# power.net
KiCad netlist of a schematic drawn in Altium Designer
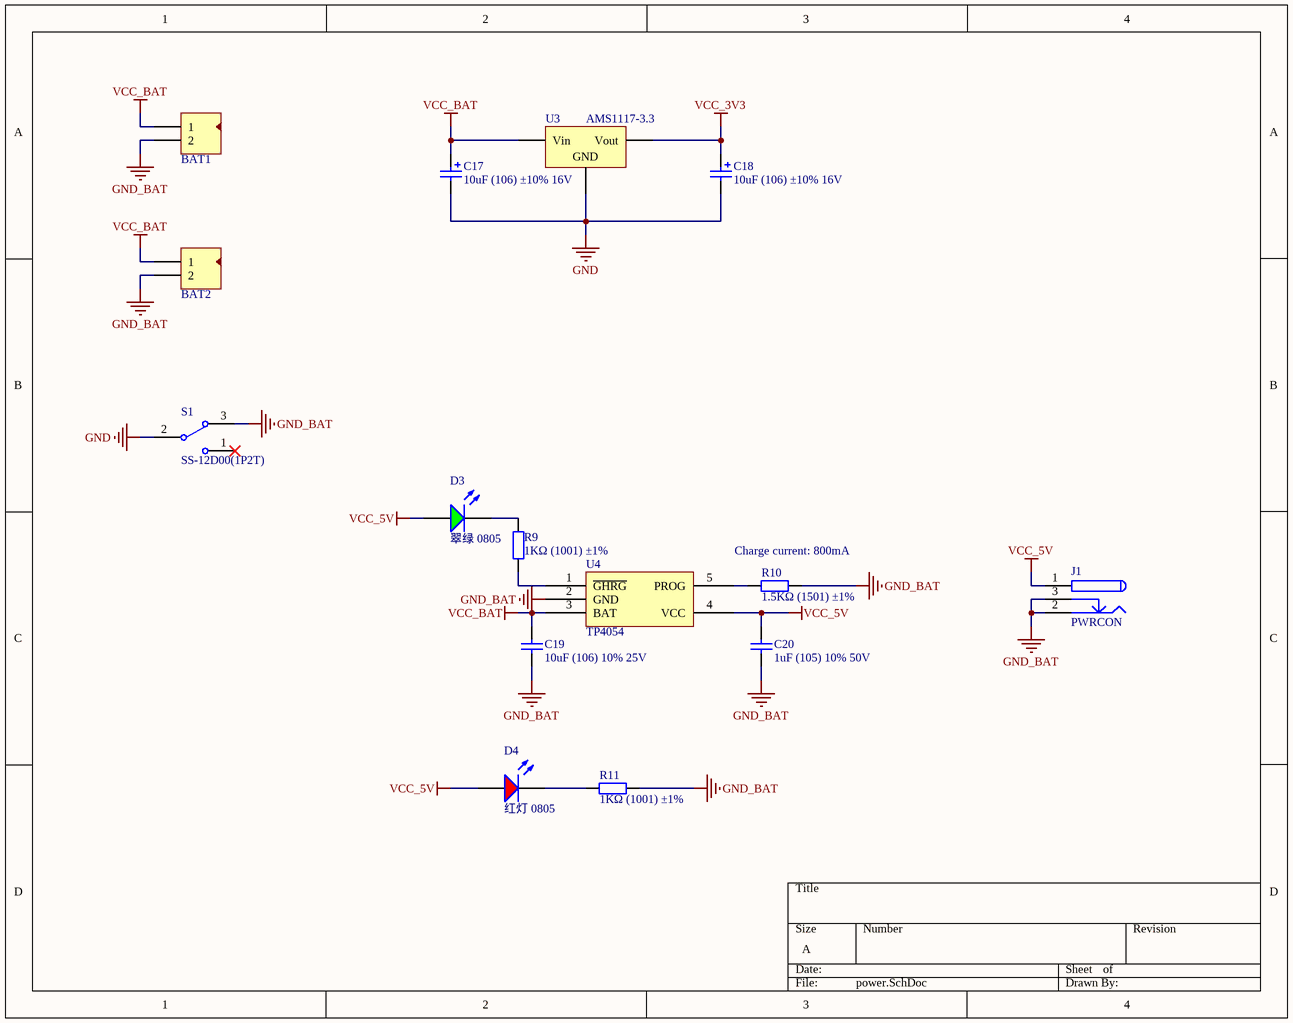
[diagram p0: power.SchDoc]

(export (version "E")
  (design (tool "Eeschema 10.0.6"))
  (components
    (comp (ref "C17")
      (value "10uF (106) ±10% 16V")
      (footprint "LC-CASE-A_3216")
      (description "钽电容")
      (libsource (lib "Miscellaneous Devices LC") (part "3216 10uF (106) 10% 16V"))
    )
    (comp (ref "C18")
      (value "10uF (106) ±10% 16V")
      (footprint "LC-CASE-A_3216")
      (description "钽电容")
      (libsource (lib "Miscellaneous Devices LC") (part "3216 10uF (106) 10% 16V"))
    )
    (comp (ref "C19")
      (value "10uF (106) 10% 25V")
      (footprint "LC-0805_C")
      (description "贴片电容")
      (libsource (lib "Miscellaneous Devices LC") (part "0805 10uF (106) 10% 25V"))
    )
    (comp (ref "C20")
      (value "1uF (105) 10% 50V")
      (footprint "LC-0805_C")
      (description "贴片电容")
      (libsource (lib "Miscellaneous Devices LC") (part "0805 1uF (105) 10% 50V"))
    )
    (comp (ref "D3")
      (value "翠绿 0805")
      (footprint "LC-0805_LED_S1")
      (description "发光二极管")
      (libsource (lib "Miscellaneous Devices LC") (part "0805 翠绿"))
    )
    (comp (ref "D4")
      (value "红灯 0805")
      (footprint "LC-0805_LED_S1")
      (description "发光二极管")
      (libsource (lib "Miscellaneous Devices LC") (part "0805 红灯"))
    )
    (comp (ref "J1")
      (value "PWRCON")
      (footprint "DC-005")
      (description "直流电源端子")
      (fields (field (name "PUBLISHER") "Altium Limited"))
      (libsource (lib "HDR_Fszhang") (part "PWRCON"))
    )
    (comp (ref "P8")
      (value "BAT1")
      (footprint "HDR2X1-2.54")
      (description "接插件")
      (fields (field (name "PUBLISHER") "Altium Limited"))
      (libsource (lib "HDR_Fszhang") (part "Header 2"))
    )
    (comp (ref "P9")
      (value "BAT2")
      (footprint "HDR2X1-2.54")
      (description "接插件")
      (fields (field (name "PUBLISHER") "Altium Limited"))
      (libsource (lib "HDR_Fszhang") (part "Header 2"))
    )
    (comp (ref "R9")
      (value "1KΩ (1001) ±1%")
      (footprint "LC-0805_R")
      (description "贴片电阻")
      (libsource (lib "Miscellaneous Devices LC") (part "0805 1KΩ (1001) 1%"))
    )
    (comp (ref "R10")
      (value "1.5KΩ (1501) ±1%")
      (footprint "LC-0805_R")
      (description "贴片电阻")
      (libsource (lib "Miscellaneous Devices LC") (part "0805 1.5KΩ (1501) 1%"))
    )
    (comp (ref "R11")
      (value "1KΩ (1001) ±1%")
      (footprint "LC-0805_R")
      (description "贴片电阻")
      (libsource (lib "") (part "0805 1KΩ (1001) 1%_1"))
    )
    (comp (ref "S1")
      (value "SS-12D00(1P2T)")
      (footprint "XH2.54-3P")
      (description "开关")
      (fields (field (name "PUBLISHER") "Altium Limited"))
      (libsource (lib "HanZ_Library") (part "SW-SPDT"))
    )
    (comp (ref "U3")
      (value "AMS1117-3.3")
      (footprint "LC-SOT-223")
      (description "低压差线性稳压(LDO)")
      (libsource (lib "Miscellaneous Devices LC") (part "SOT-223 AMS1117-3.3"))
    )
    (comp (ref "U4")
      (value "TP4054")
      (footprint "LC-SOT-23-5")
      (description "电池电源管理")
      (libsource (lib "Miscellaneous Devices LC") (part "TP4054"))
    )
  )
  (nets
    (net (code "1") (name "GND") (class "Default")
      (node (ref "C17") (pin "2") (pinfunction "2_2") (pintype "passive"))
      (node (ref "C18") (pin "2") (pinfunction "2_2") (pintype "passive"))
      (node (ref "S1") (pin "2") (pinfunction "2_2") (pintype "passive"))
      (node (ref "U3") (pin "1") (pinfunction "GND_1") (pintype "passive"))
    )
    (net (code "2") (name "GND_BAT") (class "Default")
      (node (ref "C19") (pin "1") (pinfunction "1_1") (pintype "passive"))
      (node (ref "C20") (pin "1") (pinfunction "1_1") (pintype "passive"))
      (node (ref "J1") (pin "2") (pinfunction "2_2") (pintype "power_in"))
      (node (ref "J1") (pin "3") (pinfunction "3_3") (pintype "power_in"))
      (node (ref "P8") (pin "2") (pinfunction "2_2") (pintype "passive"))
      (node (ref "P9") (pin "2") (pinfunction "2_2") (pintype "passive"))
      (node (ref "R10") (pin "2") (pinfunction "2_2") (pintype "passive"))
      (node (ref "R11") (pin "1") (pinfunction "1_1") (pintype "passive"))
      (node (ref "S1") (pin "3") (pinfunction "3_3") (pintype "passive"))
      (node (ref "U4") (pin "2") (pinfunction "GND_2") (pintype "passive"))
    )
    (net (code "3") (name "Net-(D3-PadK)") (class "Default")
      (node (ref "D3") (pin "K") (pinfunction "K_K") (pintype "passive"))
      (node (ref "R9") (pin "2") (pinfunction "2_2") (pintype "passive"))
    )
    (net (code "4") (name "Net-(D4-PadK)") (class "Default")
      (node (ref "D4") (pin "K") (pinfunction "K_K") (pintype "passive"))
      (node (ref "R11") (pin "2") (pinfunction "2_2") (pintype "passive"))
    )
    (net (code "5") (name "Net-(U4-PROG)") (class "Default")
      (node (ref "R10") (pin "1") (pinfunction "1_1") (pintype "passive"))
      (node (ref "U4") (pin "5") (pinfunction "PROG_5") (pintype "passive"))
    )
    (net (code "6") (name "Net-(U4-~{GHRG})") (class "Default")
      (node (ref "R9") (pin "1") (pinfunction "1_1") (pintype "passive"))
      (node (ref "U4") (pin "1") (pinfunction "~{GHRG}_1") (pintype "passive"))
    )
    (net (code "7") (name "VCC_3V3") (class "Default")
      (node (ref "C18") (pin "1") (pinfunction "1_1") (pintype "passive"))
      (node (ref "U3") (pin "2") (pinfunction "Vout_2") (pintype "passive"))
    )
    (net (code "8") (name "VCC_5V") (class "Default")
      (node (ref "C20") (pin "2") (pinfunction "2_2") (pintype "passive"))
      (node (ref "D3") (pin "A") (pinfunction "A_A") (pintype "passive"))
      (node (ref "D4") (pin "A") (pinfunction "A_A") (pintype "passive"))
      (node (ref "J1") (pin "1") (pinfunction "1_1") (pintype "power_in"))
      (node (ref "U4") (pin "4") (pinfunction "VCC_4") (pintype "passive"))
    )
    (net (code "9") (name "VCC_BAT") (class "Default")
      (node (ref "C17") (pin "1") (pinfunction "1_1") (pintype "passive"))
      (node (ref "C19") (pin "2") (pinfunction "2_2") (pintype "passive"))
      (node (ref "P8") (pin "1") (pinfunction "1_1") (pintype "passive"))
      (node (ref "P9") (pin "1") (pinfunction "1_1") (pintype "passive"))
      (node (ref "U3") (pin "3") (pinfunction "Vin_3") (pintype "passive"))
      (node (ref "U4") (pin "3") (pinfunction "BAT_3") (pintype "passive"))
    )
    (net (code "10") (name "unconnected-(S1-Pad1)") (class "Default")
      (node (ref "S1") (pin "1") (pinfunction "1_1") (pintype "passive+no_connect"))
    )
  )
)
